# IOTBee-Carrier_v0_11.net
KiCad netlist of a schematic drawn in EAGLE
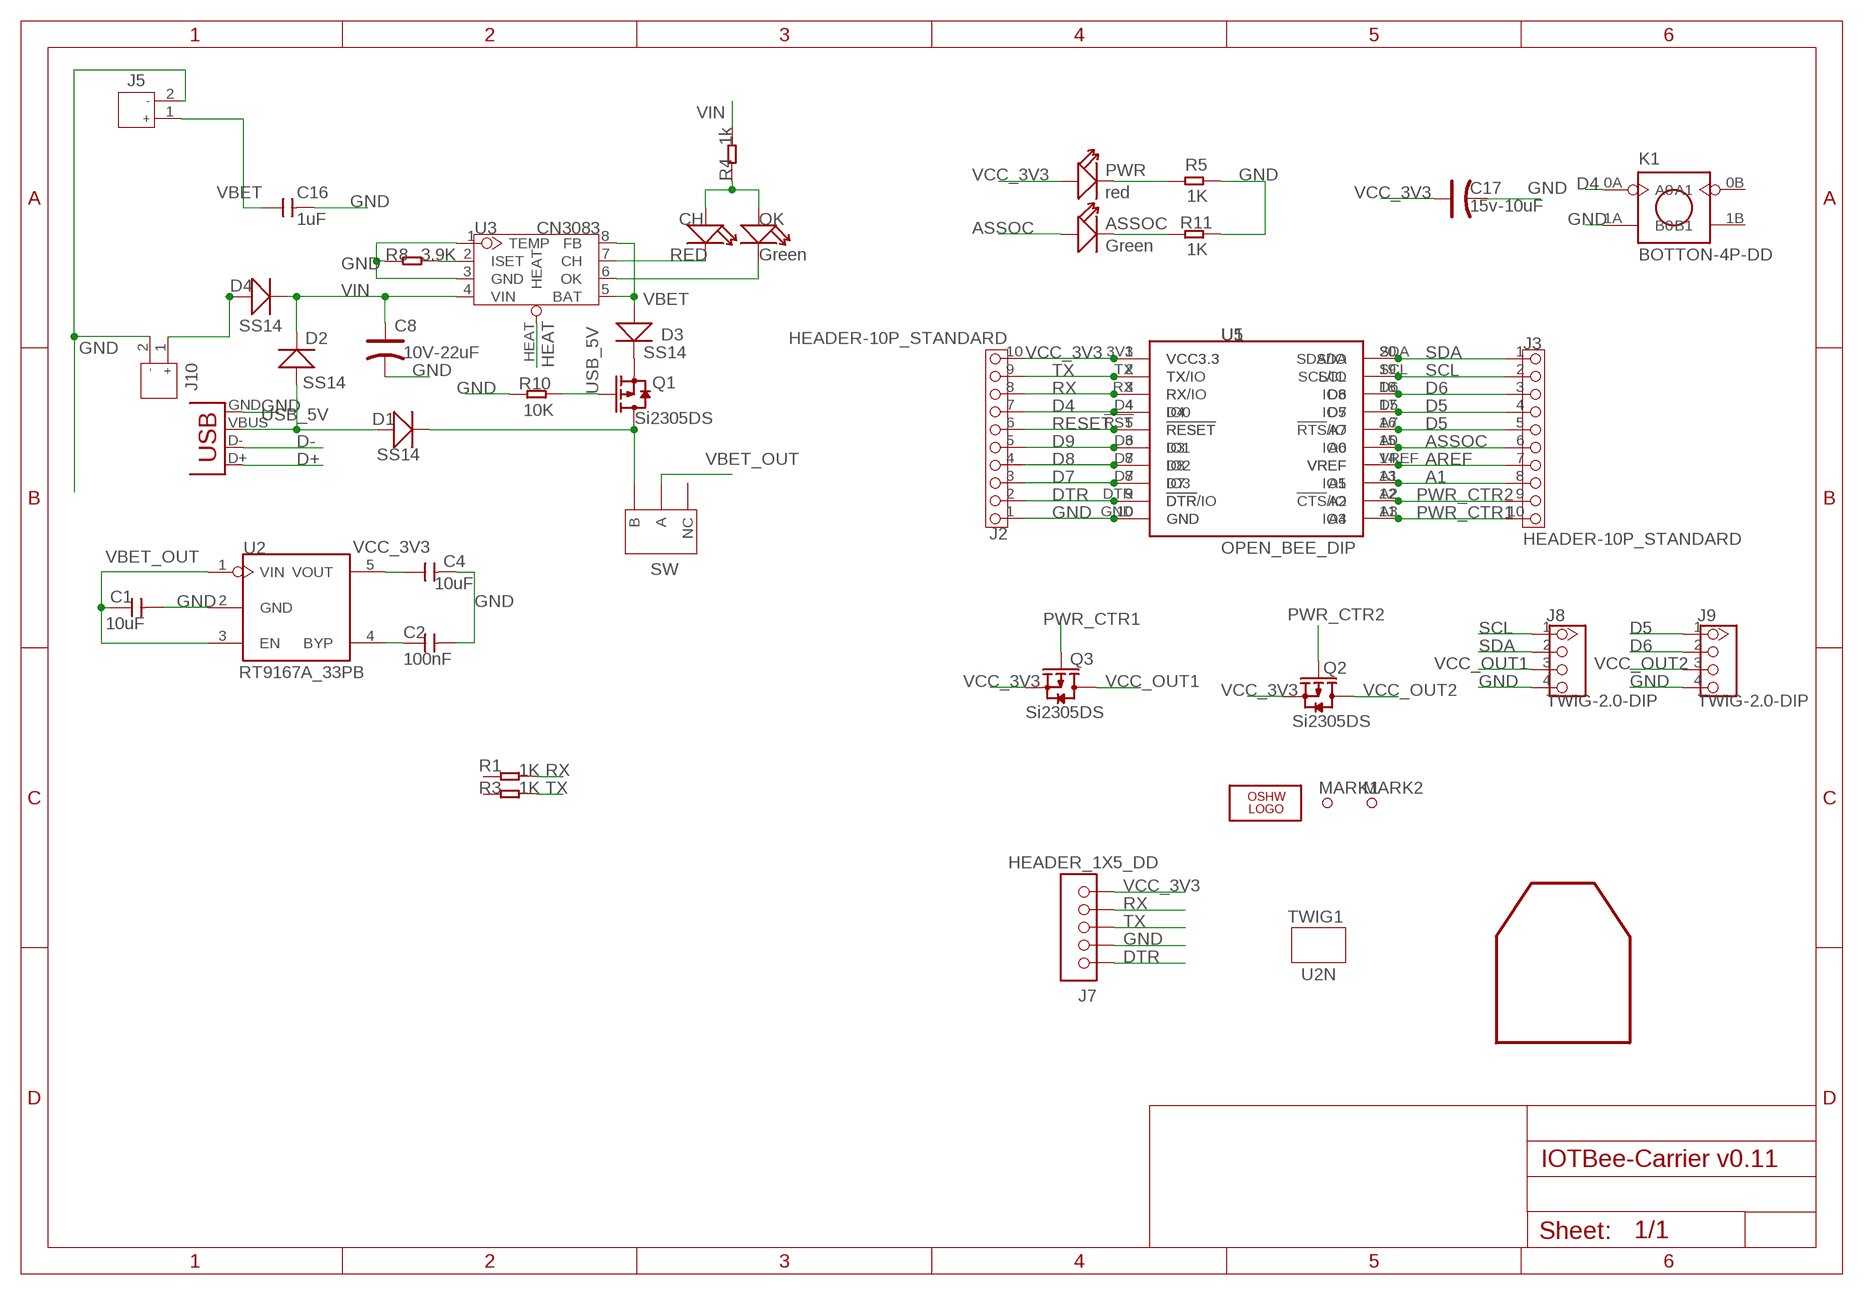
[diagram p0: schematic, sheet 1]

(export (version "E")
  (design (tool "Eeschema 10.0.6"))
  (components
    (comp (ref "ASSOC")
      (value "Green")
      (footprint "eagle-import:D0603")
      (libsource (lib "eagle-import") (part "LED-0603"))
    )
    (comp (ref "C1")
      (value "10uF")
      (footprint "eagle-import:0805")
      (libsource (lib "eagle-import") (part "C-0805"))
    )
    (comp (ref "C2")
      (value "100nF")
      (footprint "eagle-import:0603")
      (libsource (lib "eagle-import") (part "C-0603"))
    )
    (comp (ref "C4")
      (value "10uF")
      (footprint "eagle-import:0805")
      (libsource (lib "eagle-import") (part "C-0805"))
    )
    (comp (ref "C8")
      (value "10V-22uF")
      (footprint "eagle-import:AVX-B")
      (libsource (lib "eagle-import") (part "CAP_AVX_B"))
    )
    (comp (ref "C16")
      (value "1uF")
      (footprint "eagle-import:0805")
      (libsource (lib "eagle-import") (part "C-0805"))
    )
    (comp (ref "C17")
      (value "15v-10uF")
      (footprint "eagle-import:AVX-A")
      (libsource (lib "eagle-import") (part "CAP_AVX_A"))
    )
    (comp (ref "CH")
      (value "RED")
      (footprint "eagle-import:D0603")
      (libsource (lib "eagle-import") (part "LED-0603"))
    )
    (comp (ref "D1")
      (value "SS14")
      (footprint "eagle-import:D2010")
      (libsource (lib "eagle-import") (part "D-2010"))
    )
    (comp (ref "D2")
      (value "SS14")
      (footprint "eagle-import:D2010")
      (libsource (lib "eagle-import") (part "D-2010"))
    )
    (comp (ref "D3")
      (value "SS14")
      (footprint "eagle-import:D2010")
      (libsource (lib "eagle-import") (part "D-2010"))
    )
    (comp (ref "D4")
      (value "SS14")
      (footprint "eagle-import:D2010")
      (libsource (lib "eagle-import") (part "D-2010"))
    )
    (comp (ref "J2")
      (value "HEADER-10P_STANDARD")
      (footprint "eagle-import:2.54_10P")
      (libsource (lib "eagle-import") (part "HEADER-10P_STANDARD"))
    )
    (comp (ref "J3")
      (value "HEADER-10P_STANDARD")
      (footprint "eagle-import:2.54_10P")
      (libsource (lib "eagle-import") (part "HEADER-10P_STANDARD"))
    )
    (comp (ref "J5")
      (value "JST-2P-POWER-LEADED")
      (footprint "eagle-import:2P-2.0-LEADED-4.7X6.0")
      (libsource (lib "eagle-import") (part "JST-2P-POWER-LEADED"))
    )
    (comp (ref "J7")
      (value "HEADER_1X5_DD")
      (footprint "eagle-import:CK_1X5")
      (libsource (lib "eagle-import") (part "HEADER_1X5_DD"))
    )
    (comp (ref "J8")
      (value "TWIG-2.0-DIP")
      (footprint "eagle-import:2.0_1X4")
      (libsource (lib "eagle-import") (part "TWIG-2.0-DIP"))
    )
    (comp (ref "J9")
      (value "TWIG-2.0-DIP")
      (footprint "eagle-import:2.0_1X4")
      (libsource (lib "eagle-import") (part "TWIG-2.0-DIP"))
    )
    (comp (ref "J10")
      (value "JST-2P-POWER-LEADED")
      (footprint "eagle-import:2P-2.0-LEADED-4.7X6.0")
      (libsource (lib "eagle-import") (part "JST-2P-POWER-LEADED"))
    )
    (comp (ref "K1")
      (value "BOTTON-4P-DD")
      (footprint "eagle-import:BTN-S")
      (libsource (lib "eagle-import") (part "BOTTON-4P-DD"))
    )
    (comp (ref "LOGO2")
      (value "OSHW_LOGO_FILLX0200-NT")
      (footprint "eagle-import:OSHW_FILLX200_NOTEXT")
      (libsource (lib "eagle-import") (part "OSHW_LOGO_FILLX0200-NT"))
    )
    (comp (ref "MARK1")
      (value "PAD-MARK")
      (footprint "eagle-import:MARK")
      (libsource (lib "eagle-import") (part "PAD-MARK"))
    )
    (comp (ref "MARK2")
      (value "PAD-MARK")
      (footprint "eagle-import:MARK")
      (libsource (lib "eagle-import") (part "PAD-MARK"))
    )
    (comp (ref "OK")
      (value "Green")
      (footprint "eagle-import:D0603")
      (libsource (lib "eagle-import") (part "LED-0603"))
    )
    (comp (ref "PWR")
      (value "red")
      (footprint "eagle-import:D0805")
      (libsource (lib "eagle-import") (part "LED-0805"))
    )
    (comp (ref "Q1")
      (value "Si2305DS")
      (footprint "eagle-import:SOT23")
      (libsource (lib "eagle-import") (part "010-P-MOSFETSOT23"))
    )
    (comp (ref "Q2")
      (value "Si2305DS")
      (footprint "eagle-import:SOT23")
      (libsource (lib "eagle-import") (part "010-P-MOSFETSOT23"))
    )
    (comp (ref "Q3")
      (value "Si2305DS")
      (footprint "eagle-import:SOT23")
      (libsource (lib "eagle-import") (part "010-P-MOSFETSOT23"))
    )
    (comp (ref "R1")
      (value "1K")
      (footprint "eagle-import:0603")
      (libsource (lib "eagle-import") (part "R-0603"))
    )
    (comp (ref "R3")
      (value "1K")
      (footprint "eagle-import:0603")
      (libsource (lib "eagle-import") (part "R-0603"))
    )
    (comp (ref "R4")
      (value "1k")
      (footprint "eagle-import:0603")
      (libsource (lib "eagle-import") (part "R-0603"))
    )
    (comp (ref "R5")
      (value "1K")
      (footprint "eagle-import:0603")
      (libsource (lib "eagle-import") (part "R-0603"))
    )
    (comp (ref "R8")
      (value "3.9K")
      (footprint "eagle-import:0603")
      (libsource (lib "eagle-import") (part "R-0603"))
    )
    (comp (ref "R10")
      (value "10K")
      (footprint "eagle-import:0603")
      (libsource (lib "eagle-import") (part "R-0603"))
    )
    (comp (ref "R11")
      (value "1K")
      (footprint "eagle-import:0603")
      (libsource (lib "eagle-import") (part "R-0603"))
    )
    (comp (ref "SW")
      (value "SWITCH-3P")
      (footprint "eagle-import:008-SW-3P-DIP")
      (libsource (lib "eagle-import") (part "SWITCH-3P"))
    )
    (comp (ref "TWIG1")
      (value "U2N")
      (footprint "eagle-import:U2N_SILK")
      (libsource (lib "eagle-import") (part "U2N"))
    )
    (comp (ref "U$1")
      (value "WIFI_SILK")
      (footprint "eagle-import:WIFI_SILK")
      (libsource (lib "eagle-import") (part "WIFI_SILK"))
    )
    (comp (ref "U1")
      (value "OPEN_BEE_DIP")
      (footprint "eagle-import:CCBEE-PRO")
      (libsource (lib "eagle-import") (part "OPEN_BEE_DIP"))
    )
    (comp (ref "U2")
      (value "RT9167A_33PB")
      (footprint "eagle-import:SOT23-5")
      (libsource (lib "eagle-import") (part "RT9167A"))
    )
    (comp (ref "U3")
      (value "CN3083")
      (footprint "eagle-import:SOP8")
      (libsource (lib "eagle-import") (part "CN3083"))
    )
    (comp (ref "U5")
      (value "BEE-IOTBEE-IOTBEE-SOCKET")
      (footprint "eagle-import:IOT_BEE_SMD")
      (libsource (lib "eagle-import") (part "BEE-IOTBEE-IOTBEE-SOCKET"))
    )
    (comp (ref "X1")
      (value "USB-SMD-NS")
      (footprint "eagle-import:USB-MINIB-NOSTOP")
      (libsource (lib "eagle-import") (part "USB-SMD-NS"))
    )
  )
  (nets
    (net (code "1") (name "/A1") (class "Default")
      (node (ref "J3") (pin "8") (pinfunction "8_8") (pintype "bidirectional"))
      (node (ref "U1") (pin "13") (pinfunction "IO5_13") (pintype "bidirectional"))
      (node (ref "U5") (pin "A1") (pinfunction "A1_A1") (pintype "bidirectional"))
    )
    (net (code "2") (name "/AREF") (class "Default")
      (node (ref "J3") (pin "7") (pinfunction "7_7") (pintype "bidirectional"))
      (node (ref "U1") (pin "14") (pinfunction "VREF_14") (pintype "bidirectional"))
      (node (ref "U5") (pin "VREF") (pinfunction "VREF_VREF") (pintype "bidirectional"))
    )
    (net (code "3") (name "/ASSOC") (class "Default")
      (node (ref "ASSOC") (pin "+") (pinfunction "+_+") (pintype "passive"))
      (node (ref "J3") (pin "6") (pinfunction "6_6") (pintype "bidirectional"))
      (node (ref "U1") (pin "15") (pinfunction "IO6_15") (pintype "bidirectional"))
      (node (ref "U5") (pin "A0") (pinfunction "A0_A0") (pintype "bidirectional"))
    )
    (net (code "4") (name "/D+") (class "Default")
      (node (ref "X1") (pin "D+") (pinfunction "D+_D+") (pintype "bidirectional"))
    )
    (net (code "5") (name "/D-") (class "Default")
      (node (ref "X1") (pin "D-") (pinfunction "D-_D-") (pintype "bidirectional"))
    )
    (net (code "6") (name "/D4") (class "Default")
      (node (ref "J2") (pin "7") (pinfunction "7_7") (pintype "bidirectional"))
      (node (ref "K1") (pin "0A") (pinfunction "A0_0A") (pintype "bidirectional"))
      (node (ref "U1") (pin "4") (pinfunction "IO0_4") (pintype "bidirectional"))
      (node (ref "U5") (pin "D4") (pinfunction "D4_D4") (pintype "bidirectional"))
    )
    (net (code "7") (name "/D5") (class "Default")
      (node (ref "J3") (pin "4") (pinfunction "4_4") (pintype "bidirectional"))
      (node (ref "J3") (pin "5") (pinfunction "5_5") (pintype "bidirectional"))
      (node (ref "J9") (pin "1") (pinfunction "1_1") (pintype "bidirectional"))
      (node (ref "U1") (pin "16") (pinfunction "~{RTS}/IO_16") (pintype "bidirectional"))
      (node (ref "U1") (pin "17") (pinfunction "IO7_17") (pintype "bidirectional"))
      (node (ref "U5") (pin "A7") (pinfunction "A7_A7") (pintype "bidirectional"))
      (node (ref "U5") (pin "D5") (pinfunction "D5_D5") (pintype "bidirectional"))
    )
    (net (code "8") (name "/D6") (class "Default")
      (node (ref "J3") (pin "3") (pinfunction "3_3") (pintype "bidirectional"))
      (node (ref "J9") (pin "2") (pinfunction "2_2") (pintype "bidirectional"))
      (node (ref "U1") (pin "18") (pinfunction "IO8_18") (pintype "bidirectional"))
      (node (ref "U5") (pin "D6") (pinfunction "D6_D6") (pintype "bidirectional"))
    )
    (net (code "9") (name "/D7") (class "Default")
      (node (ref "J2") (pin "3") (pinfunction "3_3") (pintype "bidirectional"))
      (node (ref "U1") (pin "8") (pinfunction "IO3_8") (pintype "bidirectional"))
      (node (ref "U5") (pin "D7") (pinfunction "D7_D7") (pintype "bidirectional"))
    )
    (net (code "10") (name "/D8") (class "Default")
      (node (ref "J2") (pin "4") (pinfunction "4_4") (pintype "bidirectional"))
      (node (ref "U1") (pin "7") (pinfunction "IO2_7") (pintype "bidirectional"))
      (node (ref "U5") (pin "D8") (pinfunction "D8_D8") (pintype "bidirectional"))
    )
    (net (code "11") (name "/D9") (class "Default")
      (node (ref "J2") (pin "5") (pinfunction "5_5") (pintype "bidirectional"))
      (node (ref "U1") (pin "6") (pinfunction "IO1_6") (pintype "bidirectional"))
      (node (ref "U5") (pin "D3") (pinfunction "D3_D3") (pintype "bidirectional"))
    )
    (net (code "12") (name "/DTR") (class "Default")
      (node (ref "J2") (pin "2") (pinfunction "2_2") (pintype "bidirectional"))
      (node (ref "J7") (pin "1") (pinfunction "1_1") (pintype "bidirectional"))
      (node (ref "U1") (pin "9") (pinfunction "~{DTR}/IO_9") (pintype "bidirectional"))
      (node (ref "U5") (pin "DTR") (pinfunction "~{DTR}_DTR") (pintype "bidirectional"))
    )
    (net (code "13") (name "/GND") (class "Default")
      (node (ref "C1") (pin "2") (pinfunction "2_2") (pintype "passive"))
      (node (ref "C16") (pin "2") (pinfunction "2_2") (pintype "passive"))
      (node (ref "C17") (pin "-") (pinfunction "-_-") (pintype "passive"))
      (node (ref "C2") (pin "2") (pinfunction "2_2") (pintype "passive"))
      (node (ref "C4") (pin "2") (pinfunction "2_2") (pintype "passive"))
      (node (ref "C8") (pin "-") (pinfunction "-_-") (pintype "passive"))
      (node (ref "J10") (pin "2") (pinfunction "P$2_2") (pintype "bidirectional"))
      (node (ref "J2") (pin "1") (pinfunction "1_1") (pintype "bidirectional"))
      (node (ref "J5") (pin "2") (pinfunction "P$2_2") (pintype "bidirectional"))
      (node (ref "J7") (pin "2") (pinfunction "2_2") (pintype "bidirectional"))
      (node (ref "J8") (pin "4") (pinfunction "4_4") (pintype "bidirectional"))
      (node (ref "J9") (pin "4") (pinfunction "4_4") (pintype "bidirectional"))
      (node (ref "K1") (pin "1A") (pinfunction "B0_1A") (pintype "bidirectional"))
      (node (ref "R10") (pin "1") (pinfunction "1_1") (pintype "passive"))
      (node (ref "R11") (pin "1") (pinfunction "1_1") (pintype "passive"))
      (node (ref "R5") (pin "1") (pinfunction "1_1") (pintype "passive"))
      (node (ref "R8") (pin "1") (pinfunction "1_1") (pintype "passive"))
      (node (ref "U1") (pin "10") (pinfunction "GND_10") (pintype "bidirectional"))
      (node (ref "U2") (pin "2") (pinfunction "GND_2") (pintype "bidirectional"))
      (node (ref "U3") (pin "1") (pinfunction "TEMP_1") (pintype "bidirectional"))
      (node (ref "U3") (pin "3") (pinfunction "GND_3") (pintype "bidirectional"))
      (node (ref "U5") (pin "GND") (pinfunction "GND_GND") (pintype "bidirectional"))
      (node (ref "X1") (pin "GND") (pinfunction "GND_GND") (pintype "bidirectional"))
    )
    (net (code "14") (name "/HEAT") (class "Default")
      (node (ref "U3") (pin "HEAT") (pinfunction "HEAT_HEAT") (pintype "bidirectional"))
    )
    (net (code "15") (name "/PWR_CTR1") (class "Default")
      (node (ref "J3") (pin "10") (pinfunction "10_10") (pintype "bidirectional"))
      (node (ref "Q3") (pin "1") (pinfunction "G_1") (pintype "passive"))
      (node (ref "U1") (pin "11") (pinfunction "IO4_11") (pintype "bidirectional"))
      (node (ref "U5") (pin "A3") (pinfunction "A3_A3") (pintype "bidirectional"))
    )
    (net (code "16") (name "/PWR_CTR2") (class "Default")
      (node (ref "J3") (pin "9") (pinfunction "9_9") (pintype "bidirectional"))
      (node (ref "Q2") (pin "1") (pinfunction "G_1") (pintype "passive"))
      (node (ref "U1") (pin "12") (pinfunction "~{CTS}/IO_12") (pintype "bidirectional"))
      (node (ref "U5") (pin "A2") (pinfunction "A2_A2") (pintype "bidirectional"))
    )
    (net (code "17") (name "/RESET") (class "Default")
      (node (ref "J2") (pin "6") (pinfunction "6_6") (pintype "bidirectional"))
      (node (ref "U1") (pin "5") (pinfunction "~{RESET}_5") (pintype "bidirectional"))
      (node (ref "U5") (pin "!RST") (pinfunction "~{RESET}_!RST") (pintype "bidirectional"))
    )
    (net (code "18") (name "/RX") (class "Default")
      (node (ref "J2") (pin "8") (pinfunction "8_8") (pintype "bidirectional"))
      (node (ref "J7") (pin "4") (pinfunction "4_4") (pintype "bidirectional"))
      (node (ref "R1") (pin "2") (pinfunction "2_2") (pintype "passive"))
      (node (ref "U1") (pin "3") (pinfunction "RX/IO_3") (pintype "bidirectional"))
      (node (ref "U5") (pin "RX") (pinfunction "RX_RX") (pintype "bidirectional"))
    )
    (net (code "19") (name "/SCL") (class "Default")
      (node (ref "J3") (pin "2") (pinfunction "2_2") (pintype "bidirectional"))
      (node (ref "J8") (pin "1") (pinfunction "1_1") (pintype "bidirectional"))
      (node (ref "U1") (pin "19") (pinfunction "SCL/IO_19") (pintype "bidirectional"))
      (node (ref "U5") (pin "SCL") (pinfunction "SCL_SCL") (pintype "bidirectional"))
    )
    (net (code "20") (name "/SDA") (class "Default")
      (node (ref "J3") (pin "1") (pinfunction "1_1") (pintype "bidirectional"))
      (node (ref "J8") (pin "2") (pinfunction "2_2") (pintype "bidirectional"))
      (node (ref "U1") (pin "20") (pinfunction "SDA/IO_20") (pintype "bidirectional"))
      (node (ref "U5") (pin "SDA") (pinfunction "SDA_SDA") (pintype "bidirectional"))
    )
    (net (code "21") (name "/TX") (class "Default")
      (node (ref "J2") (pin "9") (pinfunction "9_9") (pintype "bidirectional"))
      (node (ref "J7") (pin "3") (pinfunction "3_3") (pintype "bidirectional"))
      (node (ref "R3") (pin "2") (pinfunction "2_2") (pintype "passive"))
      (node (ref "U1") (pin "2") (pinfunction "TX/IO_2") (pintype "bidirectional"))
      (node (ref "U5") (pin "TX") (pinfunction "TX_TX") (pintype "bidirectional"))
    )
    (net (code "22") (name "/USB_5V") (class "Default")
      (node (ref "D1") (pin "+") (pinfunction "+_+") (pintype "passive"))
      (node (ref "D2") (pin "+") (pinfunction "+_+") (pintype "passive"))
      (node (ref "Q1") (pin "1") (pinfunction "G_1") (pintype "passive"))
      (node (ref "R10") (pin "2") (pinfunction "2_2") (pintype "passive"))
      (node (ref "X1") (pin "VBUS") (pinfunction "VBUS_VBUS") (pintype "bidirectional"))
    )
    (net (code "23") (name "/VBET") (class "Default")
      (node (ref "C16") (pin "1") (pinfunction "1_1") (pintype "passive"))
      (node (ref "D3") (pin "+") (pinfunction "+_+") (pintype "passive"))
      (node (ref "J5") (pin "1") (pinfunction "P$1_1") (pintype "bidirectional"))
      (node (ref "U3") (pin "5") (pinfunction "BAT_5") (pintype "bidirectional"))
      (node (ref "U3") (pin "8") (pinfunction "FB_8") (pintype "bidirectional"))
    )
    (net (code "24") (name "/VBET_OUT") (class "Default")
      (node (ref "C1") (pin "1") (pinfunction "1_1") (pintype "passive"))
      (node (ref "SW") (pin "P$2") (pinfunction "A_P$2") (pintype "bidirectional"))
      (node (ref "U2") (pin "1") (pinfunction "VIN_1") (pintype "bidirectional"))
      (node (ref "U2") (pin "3") (pinfunction "EN_3") (pintype "bidirectional"))
    )
    (net (code "25") (name "/VCC_3V3") (class "Default")
      (node (ref "C17") (pin "+") (pinfunction "+_+") (pintype "passive"))
      (node (ref "C4") (pin "1") (pinfunction "1_1") (pintype "passive"))
      (node (ref "J2") (pin "10") (pinfunction "10_10") (pintype "bidirectional"))
      (node (ref "J7") (pin "5") (pinfunction "5_5") (pintype "bidirectional"))
      (node (ref "PWR") (pin "+") (pinfunction "+_+") (pintype "passive"))
      (node (ref "Q2") (pin "2") (pinfunction "S_2") (pintype "passive"))
      (node (ref "Q3") (pin "2") (pinfunction "S_2") (pintype "passive"))
      (node (ref "U1") (pin "1") (pinfunction "VCC3.3_1") (pintype "bidirectional"))
      (node (ref "U2") (pin "5") (pinfunction "VOUT_5") (pintype "bidirectional"))
      (node (ref "U5") (pin "3V3") (pinfunction "VCC3.3_3V3") (pintype "bidirectional"))
    )
    (net (code "26") (name "/VCC_OUT1") (class "Default")
      (node (ref "J8") (pin "3") (pinfunction "3_3") (pintype "bidirectional"))
      (node (ref "Q3") (pin "3") (pinfunction "D_3") (pintype "passive"))
    )
    (net (code "27") (name "/VCC_OUT2") (class "Default")
      (node (ref "J9") (pin "3") (pinfunction "3_3") (pintype "bidirectional"))
      (node (ref "Q2") (pin "3") (pinfunction "D_3") (pintype "passive"))
    )
    (net (code "28") (name "/VIN") (class "Default")
      (node (ref "C8") (pin "+") (pinfunction "+_+") (pintype "passive"))
      (node (ref "D2") (pin "-") (pinfunction "-_-") (pintype "passive"))
      (node (ref "D4") (pin "-") (pinfunction "-_-") (pintype "passive"))
      (node (ref "R4") (pin "2") (pinfunction "2_2") (pintype "passive"))
      (node (ref "U3") (pin "4") (pinfunction "VIN_4") (pintype "bidirectional"))
    )
    (net (code "29") (name "Net-(ASSOC-Pad-)") (class "Default")
      (node (ref "ASSOC") (pin "-") (pinfunction "-_-") (pintype "passive"))
      (node (ref "R11") (pin "2") (pinfunction "2_2") (pintype "passive"))
    )
    (net (code "30") (name "Net-(CH-Pad+)") (class "Default")
      (node (ref "CH") (pin "+") (pinfunction "+_+") (pintype "passive"))
      (node (ref "OK") (pin "+") (pinfunction "+_+") (pintype "passive"))
      (node (ref "R4") (pin "1") (pinfunction "1_1") (pintype "passive"))
    )
    (net (code "31") (name "Net-(J10-P$1)") (class "Default")
      (node (ref "D4") (pin "+") (pinfunction "+_+") (pintype "passive"))
      (node (ref "J10") (pin "1") (pinfunction "P$1_1") (pintype "bidirectional"))
    )
    (net (code "32") (name "Net-(PWR-Pad-)") (class "Default")
      (node (ref "PWR") (pin "-") (pinfunction "-_-") (pintype "passive"))
      (node (ref "R5") (pin "2") (pinfunction "2_2") (pintype "passive"))
    )
    (net (code "33") (name "Net-(Q1-D)") (class "Default")
      (node (ref "D1") (pin "-") (pinfunction "-_-") (pintype "passive"))
      (node (ref "Q1") (pin "3") (pinfunction "D_3") (pintype "passive"))
      (node (ref "SW") (pin "P$3") (pinfunction "B_P$3") (pintype "bidirectional"))
    )
    (net (code "34") (name "Net-(Q1-S)") (class "Default")
      (node (ref "D3") (pin "-") (pinfunction "-_-") (pintype "passive"))
      (node (ref "Q1") (pin "2") (pinfunction "S_2") (pintype "passive"))
    )
    (net (code "35") (name "Net-(U2-BYP)") (class "Default")
      (node (ref "C2") (pin "1") (pinfunction "1_1") (pintype "passive"))
      (node (ref "U2") (pin "4") (pinfunction "BYP_4") (pintype "bidirectional"))
    )
    (net (code "36") (name "Net-(U3-CH)") (class "Default")
      (node (ref "CH") (pin "-") (pinfunction "-_-") (pintype "passive"))
      (node (ref "U3") (pin "7") (pinfunction "CH_7") (pintype "bidirectional"))
    )
    (net (code "37") (name "Net-(U3-ISET)") (class "Default")
      (node (ref "R8") (pin "2") (pinfunction "2_2") (pintype "passive"))
      (node (ref "U3") (pin "2") (pinfunction "ISET_2") (pintype "bidirectional"))
    )
    (net (code "38") (name "Net-(U3-OK)") (class "Default")
      (node (ref "OK") (pin "-") (pinfunction "-_-") (pintype "passive"))
      (node (ref "U3") (pin "6") (pinfunction "OK_6") (pintype "bidirectional"))
    )
    (net (code "39") (name "unconnected-(K1-A1-Pad0B)") (class "Default")
      (node (ref "K1") (pin "0B") (pinfunction "A1_0B") (pintype "bidirectional"))
    )
    (net (code "40") (name "unconnected-(K1-B1-Pad1B)") (class "Default")
      (node (ref "K1") (pin "1B") (pinfunction "B1_1B") (pintype "bidirectional"))
    )
    (net (code "41") (name "unconnected-(R1-Pad1)") (class "Default")
      (node (ref "R1") (pin "1") (pinfunction "1_1") (pintype "passive"))
    )
    (net (code "42") (name "unconnected-(R3-Pad1)") (class "Default")
      (node (ref "R3") (pin "1") (pinfunction "1_1") (pintype "passive"))
    )
    (net (code "43") (name "unconnected-(SW-NC-PadP$1)") (class "Default")
      (node (ref "SW") (pin "P$1") (pinfunction "NC_P$1") (pintype "no_connect"))
    )
  )
)
